# SOC_PINOUT.net
KiCad netlist of a schematic drawn in Altium Designer
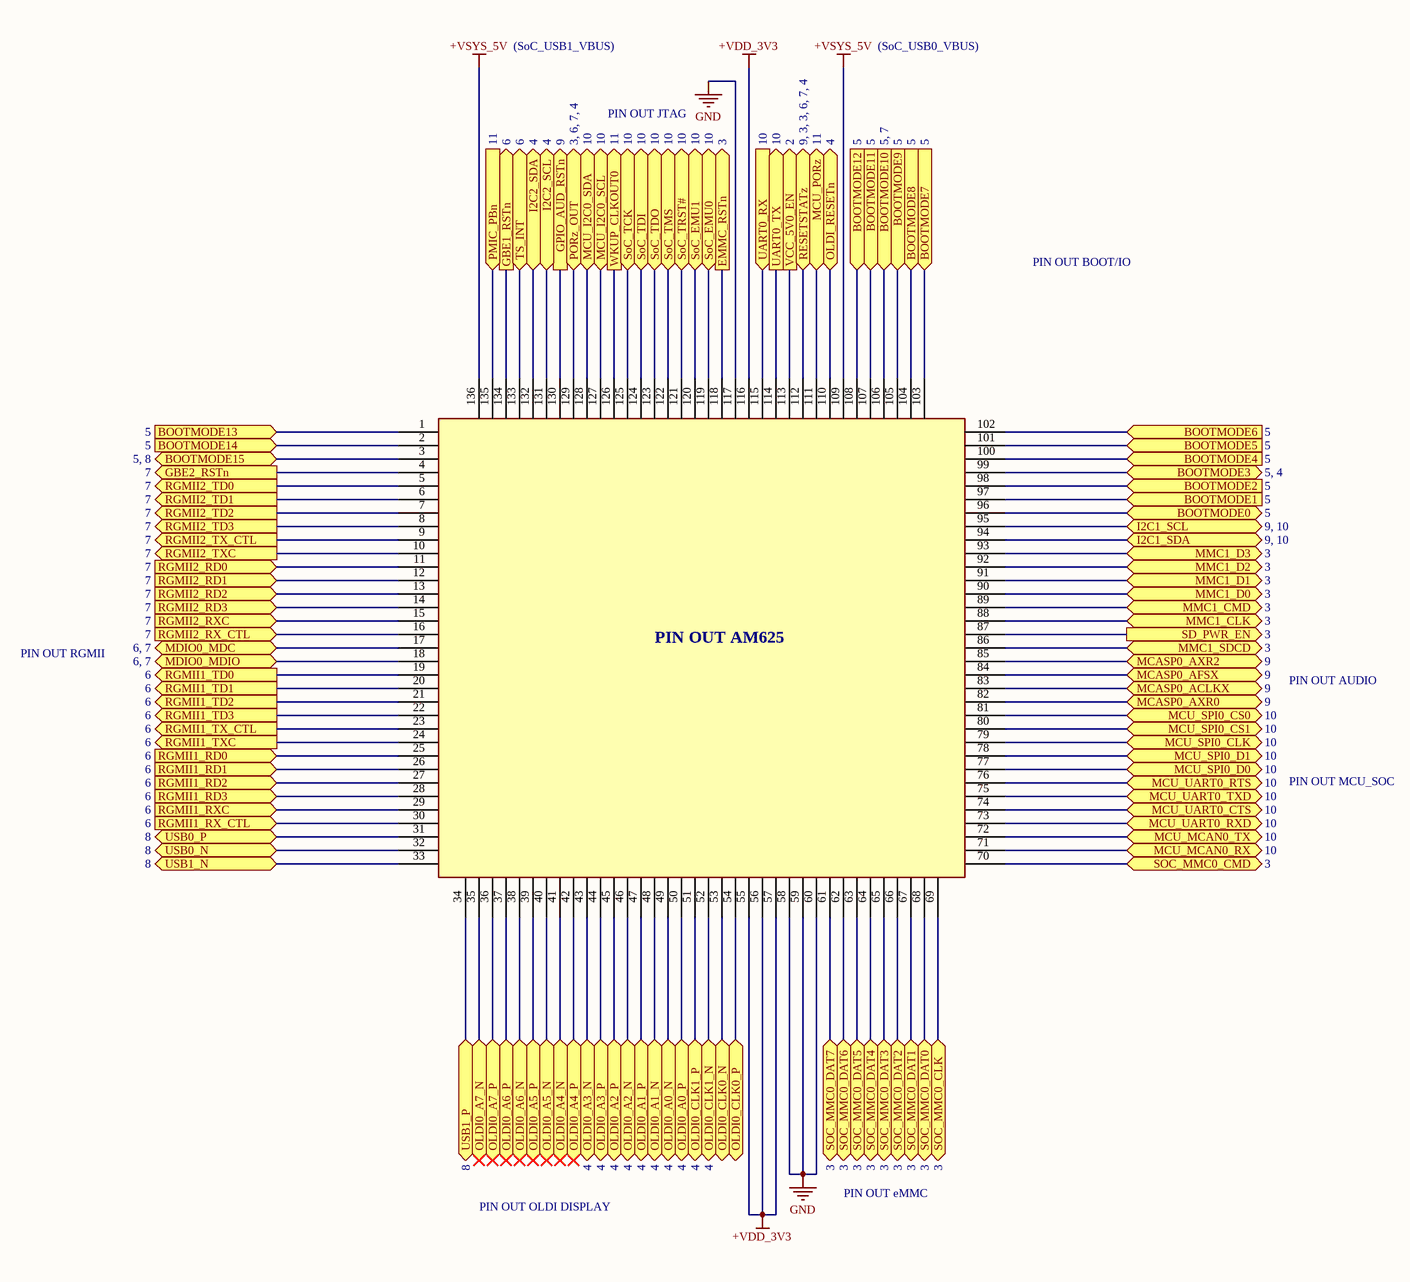
[diagram p0: SOC PINOUT.SchDoc]

(export (version "E")
  (design (tool "Eeschema 10.0.6"))
  (components
    (comp (ref "PIN1101")
      (value "Pin OUT AM625")
      (footprint "PIN_OUT AM625 - 136PIN")
      (libsource (lib "Schlib SOM AM625") (part "PIN_OUT"))
    )
  )
  (nets
    (net (code "1") (name "+VDD_3V3") (class "Default")
      (node (ref "PIN1101") (pin "116") (pinfunction "116_116") (pintype "passive"))
      (node (ref "PIN1101") (pin "55") (pinfunction "55_55") (pintype "passive"))
      (node (ref "PIN1101") (pin "56") (pinfunction "56_56") (pintype "passive"))
      (node (ref "PIN1101") (pin "57") (pinfunction "57_57") (pintype "passive"))
    )
    (net (code "2") (name "+VSYS_5V") (class "Default")
      (node (ref "PIN1101") (pin "109") (pinfunction "109_109") (pintype "passive"))
      (node (ref "PIN1101") (pin "136") (pinfunction "136_136") (pintype "passive"))
    )
    (net (code "3") (name "/BOOTMODE0") (class "Default")
      (node (ref "PIN1101") (pin "96") (pinfunction "96_96") (pintype "passive"))
    )
    (net (code "4") (name "/BOOTMODE1") (class "Default")
      (node (ref "PIN1101") (pin "97") (pinfunction "97_97") (pintype "passive"))
    )
    (net (code "5") (name "/BOOTMODE2") (class "Default")
      (node (ref "PIN1101") (pin "98") (pinfunction "98_98") (pintype "passive"))
    )
    (net (code "6") (name "/BOOTMODE3") (class "Default")
      (node (ref "PIN1101") (pin "99") (pinfunction "99_99") (pintype "passive"))
    )
    (net (code "7") (name "/BOOTMODE4") (class "Default")
      (node (ref "PIN1101") (pin "100") (pinfunction "100_100") (pintype "passive"))
    )
    (net (code "8") (name "/BOOTMODE5") (class "Default")
      (node (ref "PIN1101") (pin "101") (pinfunction "101_101") (pintype "passive"))
    )
    (net (code "9") (name "/BOOTMODE6") (class "Default")
      (node (ref "PIN1101") (pin "102") (pinfunction "102_102") (pintype "passive"))
    )
    (net (code "10") (name "/BOOTMODE7") (class "Default")
      (node (ref "PIN1101") (pin "103") (pinfunction "103_103") (pintype "passive"))
    )
    (net (code "11") (name "/BOOTMODE8") (class "Default")
      (node (ref "PIN1101") (pin "104") (pinfunction "104_104") (pintype "passive"))
    )
    (net (code "12") (name "/BOOTMODE9") (class "Default")
      (node (ref "PIN1101") (pin "105") (pinfunction "105_105") (pintype "passive"))
    )
    (net (code "13") (name "/BOOTMODE10") (class "Default")
      (node (ref "PIN1101") (pin "106") (pinfunction "106_106") (pintype "passive"))
    )
    (net (code "14") (name "/BOOTMODE11") (class "Default")
      (node (ref "PIN1101") (pin "107") (pinfunction "107_107") (pintype "passive"))
    )
    (net (code "15") (name "/BOOTMODE12") (class "Default")
      (node (ref "PIN1101") (pin "108") (pinfunction "108_108") (pintype "passive"))
    )
    (net (code "16") (name "/BOOTMODE13") (class "Default")
      (node (ref "PIN1101") (pin "1") (pinfunction "1_1") (pintype "passive"))
    )
    (net (code "17") (name "/BOOTMODE14") (class "Default")
      (node (ref "PIN1101") (pin "2") (pinfunction "2_2") (pintype "passive"))
    )
    (net (code "18") (name "/BOOTMODE15") (class "Default")
      (node (ref "PIN1101") (pin "3") (pinfunction "3_3") (pintype "passive"))
    )
    (net (code "19") (name "/EMMC_RSTn") (class "Default")
      (node (ref "PIN1101") (pin "118") (pinfunction "118_118") (pintype "passive"))
    )
    (net (code "20") (name "/GBE1_RSTn") (class "Default")
      (node (ref "PIN1101") (pin "134") (pinfunction "134_134") (pintype "passive"))
    )
    (net (code "21") (name "/GBE2_RSTn") (class "Default")
      (node (ref "PIN1101") (pin "4") (pinfunction "4_4") (pintype "passive"))
    )
    (net (code "22") (name "/GPIO_AUD_RSTn") (class "Default")
      (node (ref "PIN1101") (pin "130") (pinfunction "130_130") (pintype "passive"))
    )
    (net (code "23") (name "/I2C1_SCL") (class "Default")
      (node (ref "PIN1101") (pin "95") (pinfunction "95_95") (pintype "passive"))
    )
    (net (code "24") (name "/I2C1_SDA") (class "Default")
      (node (ref "PIN1101") (pin "94") (pinfunction "94_94") (pintype "passive"))
    )
    (net (code "25") (name "/I2C2_SCL") (class "Default")
      (node (ref "PIN1101") (pin "131") (pinfunction "131_131") (pintype "passive"))
    )
    (net (code "26") (name "/I2C2_SDA") (class "Default")
      (node (ref "PIN1101") (pin "132") (pinfunction "132_132") (pintype "passive"))
    )
    (net (code "27") (name "/MCASP0_ACLKX") (class "Default")
      (node (ref "PIN1101") (pin "83") (pinfunction "83_83") (pintype "passive"))
    )
    (net (code "28") (name "/MCASP0_AFSX") (class "Default")
      (node (ref "PIN1101") (pin "84") (pinfunction "84_84") (pintype "passive"))
    )
    (net (code "29") (name "/MCASP0_AXR0") (class "Default")
      (node (ref "PIN1101") (pin "82") (pinfunction "82_82") (pintype "passive"))
    )
    (net (code "30") (name "/MCASP0_AXR2") (class "Default")
      (node (ref "PIN1101") (pin "85") (pinfunction "85_85") (pintype "passive"))
    )
    (net (code "31") (name "/MCU_I2C0_SCL") (class "Default")
      (node (ref "PIN1101") (pin "127") (pinfunction "127_127") (pintype "passive"))
    )
    (net (code "32") (name "/MCU_I2C0_SDA") (class "Default")
      (node (ref "PIN1101") (pin "128") (pinfunction "128_128") (pintype "passive"))
    )
    (net (code "33") (name "/MCU_MCAN0_RX") (class "Default")
      (node (ref "PIN1101") (pin "71") (pinfunction "71_71") (pintype "passive"))
    )
    (net (code "34") (name "/MCU_MCAN0_TX") (class "Default")
      (node (ref "PIN1101") (pin "72") (pinfunction "72_72") (pintype "passive"))
    )
    (net (code "35") (name "/MCU_PORz") (class "Default")
      (node (ref "PIN1101") (pin "111") (pinfunction "111_111") (pintype "passive"))
    )
    (net (code "36") (name "/MCU_SPI0_CLK") (class "Default")
      (node (ref "PIN1101") (pin "79") (pinfunction "79_79") (pintype "passive"))
    )
    (net (code "37") (name "/MCU_SPI0_CS0") (class "Default")
      (node (ref "PIN1101") (pin "81") (pinfunction "81_81") (pintype "passive"))
    )
    (net (code "38") (name "/MCU_SPI0_CS1") (class "Default")
      (node (ref "PIN1101") (pin "80") (pinfunction "80_80") (pintype "passive"))
    )
    (net (code "39") (name "/MCU_SPI0_D0") (class "Default")
      (node (ref "PIN1101") (pin "77") (pinfunction "77_77") (pintype "passive"))
    )
    (net (code "40") (name "/MCU_SPI0_D1") (class "Default")
      (node (ref "PIN1101") (pin "78") (pinfunction "78_78") (pintype "passive"))
    )
    (net (code "41") (name "/MCU_UART0_CTS") (class "Default")
      (node (ref "PIN1101") (pin "74") (pinfunction "74_74") (pintype "passive"))
    )
    (net (code "42") (name "/MCU_UART0_RTS") (class "Default")
      (node (ref "PIN1101") (pin "76") (pinfunction "76_76") (pintype "passive"))
    )
    (net (code "43") (name "/MCU_UART0_RXD") (class "Default")
      (node (ref "PIN1101") (pin "73") (pinfunction "73_73") (pintype "passive"))
    )
    (net (code "44") (name "/MCU_UART0_TXD") (class "Default")
      (node (ref "PIN1101") (pin "75") (pinfunction "75_75") (pintype "passive"))
    )
    (net (code "45") (name "/MDIO0_MDC") (class "Default")
      (node (ref "PIN1101") (pin "17") (pinfunction "17_17") (pintype "passive"))
    )
    (net (code "46") (name "/MDIO0_MDIO") (class "Default")
      (node (ref "PIN1101") (pin "18") (pinfunction "18_18") (pintype "passive"))
    )
    (net (code "47") (name "/MMC1_CLK") (class "Default")
      (node (ref "PIN1101") (pin "88") (pinfunction "88_88") (pintype "passive"))
    )
    (net (code "48") (name "/MMC1_CMD") (class "Default")
      (node (ref "PIN1101") (pin "89") (pinfunction "89_89") (pintype "passive"))
    )
    (net (code "49") (name "/MMC1_D0") (class "Default")
      (node (ref "PIN1101") (pin "90") (pinfunction "90_90") (pintype "passive"))
    )
    (net (code "50") (name "/MMC1_D1") (class "Default")
      (node (ref "PIN1101") (pin "91") (pinfunction "91_91") (pintype "passive"))
    )
    (net (code "51") (name "/MMC1_D2") (class "Default")
      (node (ref "PIN1101") (pin "92") (pinfunction "92_92") (pintype "passive"))
    )
    (net (code "52") (name "/MMC1_D3") (class "Default")
      (node (ref "PIN1101") (pin "93") (pinfunction "93_93") (pintype "passive"))
    )
    (net (code "53") (name "/MMC1_SDCD") (class "Default")
      (node (ref "PIN1101") (pin "86") (pinfunction "86_86") (pintype "passive"))
    )
    (net (code "54") (name "/OLDI0_A0_N") (class "Default")
      (node (ref "PIN1101") (pin "49") (pinfunction "49_49") (pintype "passive"))
    )
    (net (code "55") (name "/OLDI0_A0_P") (class "Default")
      (node (ref "PIN1101") (pin "50") (pinfunction "50_50") (pintype "passive"))
    )
    (net (code "56") (name "/OLDI0_A1_N") (class "Default")
      (node (ref "PIN1101") (pin "48") (pinfunction "48_48") (pintype "passive"))
    )
    (net (code "57") (name "/OLDI0_A1_P") (class "Default")
      (node (ref "PIN1101") (pin "47") (pinfunction "47_47") (pintype "passive"))
    )
    (net (code "58") (name "/OLDI0_A2_N") (class "Default")
      (node (ref "PIN1101") (pin "46") (pinfunction "46_46") (pintype "passive"))
    )
    (net (code "59") (name "/OLDI0_A2_P") (class "Default")
      (node (ref "PIN1101") (pin "45") (pinfunction "45_45") (pintype "passive"))
    )
    (net (code "60") (name "/OLDI0_A3_N") (class "Default")
      (node (ref "PIN1101") (pin "43") (pinfunction "43_43") (pintype "passive"))
    )
    (net (code "61") (name "/OLDI0_A3_P") (class "Default")
      (node (ref "PIN1101") (pin "44") (pinfunction "44_44") (pintype "passive"))
    )
    (net (code "62") (name "/OLDI0_A4_N") (class "Default")
      (node (ref "PIN1101") (pin "41") (pinfunction "41_41") (pintype "passive"))
    )
    (net (code "63") (name "/OLDI0_A4_P") (class "Default")
      (node (ref "PIN1101") (pin "42") (pinfunction "42_42") (pintype "passive"))
    )
    (net (code "64") (name "/OLDI0_A5_N") (class "Default")
      (node (ref "PIN1101") (pin "40") (pinfunction "40_40") (pintype "passive"))
    )
    (net (code "65") (name "/OLDI0_A5_P") (class "Default")
      (node (ref "PIN1101") (pin "39") (pinfunction "39_39") (pintype "passive"))
    )
    (net (code "66") (name "/OLDI0_A6_N") (class "Default")
      (node (ref "PIN1101") (pin "38") (pinfunction "38_38") (pintype "passive"))
    )
    (net (code "67") (name "/OLDI0_A6_P") (class "Default")
      (node (ref "PIN1101") (pin "37") (pinfunction "37_37") (pintype "passive"))
    )
    (net (code "68") (name "/OLDI0_A7_N") (class "Default")
      (node (ref "PIN1101") (pin "35") (pinfunction "35_35") (pintype "passive"))
    )
    (net (code "69") (name "/OLDI0_A7_P") (class "Default")
      (node (ref "PIN1101") (pin "36") (pinfunction "36_36") (pintype "passive"))
    )
    (net (code "70") (name "/OLDI0_CLK0_N") (class "Default")
      (node (ref "PIN1101") (pin "53") (pinfunction "53_53") (pintype "passive"))
    )
    (net (code "71") (name "/OLDI0_CLK0_P") (class "Default")
      (node (ref "PIN1101") (pin "54") (pinfunction "54_54") (pintype "passive"))
    )
    (net (code "72") (name "/OLDI0_CLK1_N") (class "Default")
      (node (ref "PIN1101") (pin "52") (pinfunction "52_52") (pintype "passive"))
    )
    (net (code "73") (name "/OLDI0_CLK1_P") (class "Default")
      (node (ref "PIN1101") (pin "51") (pinfunction "51_51") (pintype "passive"))
    )
    (net (code "74") (name "/OLDI_RESETn") (class "Default")
      (node (ref "PIN1101") (pin "110") (pinfunction "110_110") (pintype "passive"))
    )
    (net (code "75") (name "/PMIC_PBn") (class "Default")
      (node (ref "PIN1101") (pin "135") (pinfunction "135_135") (pintype "passive"))
    )
    (net (code "76") (name "/PORz_OUT") (class "Default")
      (node (ref "PIN1101") (pin "129") (pinfunction "129_129") (pintype "passive"))
    )
    (net (code "77") (name "/RESETSTATz") (class "Default")
      (node (ref "PIN1101") (pin "112") (pinfunction "112_112") (pintype "passive"))
    )
    (net (code "78") (name "/RGMII1_RD0") (class "Default")
      (node (ref "PIN1101") (pin "25") (pinfunction "25_25") (pintype "passive"))
    )
    (net (code "79") (name "/RGMII1_RD1") (class "Default")
      (node (ref "PIN1101") (pin "26") (pinfunction "26_26") (pintype "passive"))
    )
    (net (code "80") (name "/RGMII1_RD2") (class "Default")
      (node (ref "PIN1101") (pin "27") (pinfunction "27_27") (pintype "passive"))
    )
    (net (code "81") (name "/RGMII1_RD3") (class "Default")
      (node (ref "PIN1101") (pin "28") (pinfunction "28_28") (pintype "passive"))
    )
    (net (code "82") (name "/RGMII1_RXC") (class "Default")
      (node (ref "PIN1101") (pin "29") (pinfunction "29_29") (pintype "passive"))
    )
    (net (code "83") (name "/RGMII1_RX_CTL") (class "Default")
      (node (ref "PIN1101") (pin "30") (pinfunction "30_30") (pintype "passive"))
    )
    (net (code "84") (name "/RGMII1_TD0") (class "Default")
      (node (ref "PIN1101") (pin "19") (pinfunction "19_19") (pintype "passive"))
    )
    (net (code "85") (name "/RGMII1_TD1") (class "Default")
      (node (ref "PIN1101") (pin "20") (pinfunction "20_20") (pintype "passive"))
    )
    (net (code "86") (name "/RGMII1_TD2") (class "Default")
      (node (ref "PIN1101") (pin "21") (pinfunction "21_21") (pintype "passive"))
    )
    (net (code "87") (name "/RGMII1_TD3") (class "Default")
      (node (ref "PIN1101") (pin "22") (pinfunction "22_22") (pintype "passive"))
    )
    (net (code "88") (name "/RGMII1_TXC") (class "Default")
      (node (ref "PIN1101") (pin "24") (pinfunction "24_24") (pintype "passive"))
    )
    (net (code "89") (name "/RGMII1_TX_CTL") (class "Default")
      (node (ref "PIN1101") (pin "23") (pinfunction "23_23") (pintype "passive"))
    )
    (net (code "90") (name "/RGMII2_RD0") (class "Default")
      (node (ref "PIN1101") (pin "11") (pinfunction "11_11") (pintype "passive"))
    )
    (net (code "91") (name "/RGMII2_RD1") (class "Default")
      (node (ref "PIN1101") (pin "12") (pinfunction "12_12") (pintype "passive"))
    )
    (net (code "92") (name "/RGMII2_RD2") (class "Default")
      (node (ref "PIN1101") (pin "13") (pinfunction "13_13") (pintype "passive"))
    )
    (net (code "93") (name "/RGMII2_RD3") (class "Default")
      (node (ref "PIN1101") (pin "14") (pinfunction "14_14") (pintype "passive"))
    )
    (net (code "94") (name "/RGMII2_RXC") (class "Default")
      (node (ref "PIN1101") (pin "15") (pinfunction "15_15") (pintype "passive"))
    )
    (net (code "95") (name "/RGMII2_RX_CTL") (class "Default")
      (node (ref "PIN1101") (pin "16") (pinfunction "16_16") (pintype "passive"))
    )
    (net (code "96") (name "/RGMII2_TD0") (class "Default")
      (node (ref "PIN1101") (pin "5") (pinfunction "5_5") (pintype "passive"))
    )
    (net (code "97") (name "/RGMII2_TD1") (class "Default")
      (node (ref "PIN1101") (pin "6") (pinfunction "6_6") (pintype "passive"))
    )
    (net (code "98") (name "/RGMII2_TD2") (class "Default")
      (node (ref "PIN1101") (pin "7") (pinfunction "7_7") (pintype "passive"))
    )
    (net (code "99") (name "/RGMII2_TD3") (class "Default")
      (node (ref "PIN1101") (pin "8") (pinfunction "8_8") (pintype "passive"))
    )
    (net (code "100") (name "/RGMII2_TXC") (class "Default")
      (node (ref "PIN1101") (pin "10") (pinfunction "10_10") (pintype "passive"))
    )
    (net (code "101") (name "/RGMII2_TX_CTL") (class "Default")
      (node (ref "PIN1101") (pin "9") (pinfunction "9_9") (pintype "passive"))
    )
    (net (code "102") (name "/SD_PWR_EN") (class "Default")
      (node (ref "PIN1101") (pin "87") (pinfunction "87_87") (pintype "passive"))
    )
    (net (code "103") (name "/SOC_MMC0_CLK") (class "Default")
      (node (ref "PIN1101") (pin "69") (pinfunction "69_69") (pintype "passive"))
    )
    (net (code "104") (name "/SOC_MMC0_CMD") (class "Default")
      (node (ref "PIN1101") (pin "70") (pinfunction "70_70") (pintype "passive"))
    )
    (net (code "105") (name "/SOC_MMC0_DAT0") (class "Default")
      (node (ref "PIN1101") (pin "68") (pinfunction "68_68") (pintype "passive"))
    )
    (net (code "106") (name "/SOC_MMC0_DAT1") (class "Default")
      (node (ref "PIN1101") (pin "67") (pinfunction "67_67") (pintype "passive"))
    )
    (net (code "107") (name "/SOC_MMC0_DAT2") (class "Default")
      (node (ref "PIN1101") (pin "66") (pinfunction "66_66") (pintype "passive"))
    )
    (net (code "108") (name "/SOC_MMC0_DAT3") (class "Default")
      (node (ref "PIN1101") (pin "65") (pinfunction "65_65") (pintype "passive"))
    )
    (net (code "109") (name "/SOC_MMC0_DAT4") (class "Default")
      (node (ref "PIN1101") (pin "64") (pinfunction "64_64") (pintype "passive"))
    )
    (net (code "110") (name "/SOC_MMC0_DAT5") (class "Default")
      (node (ref "PIN1101") (pin "63") (pinfunction "63_63") (pintype "passive"))
    )
    (net (code "111") (name "/SOC_MMC0_DAT6") (class "Default")
      (node (ref "PIN1101") (pin "62") (pinfunction "62_62") (pintype "passive"))
    )
    (net (code "112") (name "/SOC_MMC0_DAT7") (class "Default")
      (node (ref "PIN1101") (pin "61") (pinfunction "61_61") (pintype "passive"))
    )
    (net (code "113") (name "/SoC_EMU0") (class "Default")
      (node (ref "PIN1101") (pin "119") (pinfunction "119_119") (pintype "passive"))
    )
    (net (code "114") (name "/SoC_EMU1") (class "Default")
      (node (ref "PIN1101") (pin "120") (pinfunction "120_120") (pintype "passive"))
    )
    (net (code "115") (name "/SoC_TCK") (class "Default")
      (node (ref "PIN1101") (pin "125") (pinfunction "125_125") (pintype "passive"))
    )
    (net (code "116") (name "/SoC_TDI") (class "Default")
      (node (ref "PIN1101") (pin "124") (pinfunction "124_124") (pintype "passive"))
    )
    (net (code "117") (name "/SoC_TDO") (class "Default")
      (node (ref "PIN1101") (pin "123") (pinfunction "123_123") (pintype "passive"))
    )
    (net (code "118") (name "/SoC_TMS") (class "Default")
      (node (ref "PIN1101") (pin "122") (pinfunction "122_122") (pintype "passive"))
    )
    (net (code "119") (name "/SoC_TRST#") (class "Default")
      (node (ref "PIN1101") (pin "121") (pinfunction "121_121") (pintype "passive"))
    )
    (net (code "120") (name "/TS_INT") (class "Default")
      (node (ref "PIN1101") (pin "133") (pinfunction "133_133") (pintype "passive"))
    )
    (net (code "121") (name "/UART0_RX") (class "Default")
      (node (ref "PIN1101") (pin "115") (pinfunction "115_115") (pintype "passive"))
    )
    (net (code "122") (name "/UART0_TX") (class "Default")
      (node (ref "PIN1101") (pin "114") (pinfunction "114_114") (pintype "passive"))
    )
    (net (code "123") (name "/USB0_N") (class "Default")
      (node (ref "PIN1101") (pin "32") (pinfunction "32_32") (pintype "passive"))
    )
    (net (code "124") (name "/USB0_P") (class "Default")
      (node (ref "PIN1101") (pin "31") (pinfunction "31_31") (pintype "passive"))
    )
    (net (code "125") (name "/USB1_N") (class "Default")
      (node (ref "PIN1101") (pin "33") (pinfunction "33_33") (pintype "passive"))
    )
    (net (code "126") (name "/USB1_P") (class "Default")
      (node (ref "PIN1101") (pin "34") (pinfunction "34_34") (pintype "passive"))
    )
    (net (code "127") (name "/VCC_5V0_EN") (class "Default")
      (node (ref "PIN1101") (pin "113") (pinfunction "113_113") (pintype "passive"))
    )
    (net (code "128") (name "/WKUP_CLKOUT0") (class "Default")
      (node (ref "PIN1101") (pin "126") (pinfunction "126_126") (pintype "passive"))
    )
    (net (code "129") (name "GND") (class "Default")
      (node (ref "PIN1101") (pin "117") (pinfunction "117_117") (pintype "passive"))
      (node (ref "PIN1101") (pin "58") (pinfunction "58_58") (pintype "passive"))
      (node (ref "PIN1101") (pin "59") (pinfunction "59_59") (pintype "passive"))
      (node (ref "PIN1101") (pin "60") (pinfunction "60_60") (pintype "passive"))
    )
  )
)
